# dotclox.net
KiCad netlist of a schematic drawn in EAGLE
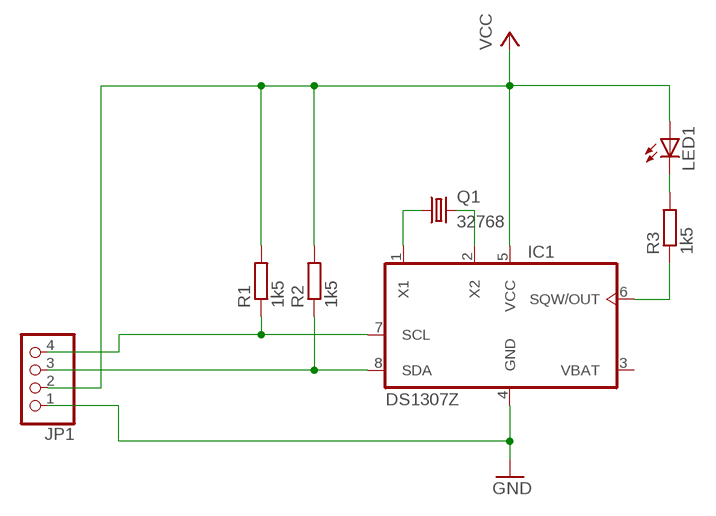
[diagram p0: schematic, sheet 1]

(export (version "E")
  (design (tool "Eeschema 10.0.6"))
  (components
    (comp (ref "IC1")
      (value "DS1307Z")
      (footprint "eagle-import:SO08")
      (libsource (lib "eagle-import") (part "DS1307Z"))
    )
    (comp (ref "JP1")
      (value "PINHD-1X4")
      (footprint "eagle-import:1X04")
      (libsource (lib "eagle-import") (part "PINHD-1X4"))
    )
    (comp (ref "LED1")
      (value "LED3MM")
      (footprint "eagle-import:LED3MM")
      (libsource (lib "eagle-import") (part "LED3MM"))
    )
    (comp (ref "Q1")
      (value "32768")
      (footprint "eagle-import:TC26H")
      (libsource (lib "eagle-import") (part "CRYSTALTC26H"))
    )
    (comp (ref "R1")
      (value "1k5")
      (footprint "eagle-import:R0603")
      (libsource (lib "eagle-import") (part "R-EU_R0603"))
    )
    (comp (ref "R2")
      (value "1k5")
      (footprint "eagle-import:R0603")
      (libsource (lib "eagle-import") (part "R-EU_R0603"))
    )
    (comp (ref "R3")
      (value "1k5")
      (footprint "eagle-import:R0603")
      (libsource (lib "eagle-import") (part "R-EU_R0603"))
    )
  )
  (nets
    (net (code "1") (name "/VBAT") (class "Default")
      (node (ref "IC1") (pin "3") (pinfunction "VBAT_3") (pintype "power_in"))
    )
    (net (code "2") (name "GND") (class "Default")
      (node (ref "IC1") (pin "4") (pinfunction "GND_4") (pintype "power_in"))
      (node (ref "JP1") (pin "1") (pinfunction "1_1") (pintype "passive"))
    )
    (net (code "3") (name "Net-(IC1-SCL)") (class "Default")
      (node (ref "IC1") (pin "7") (pinfunction "SCL_7") (pintype "bidirectional"))
      (node (ref "JP1") (pin "4") (pinfunction "4_4") (pintype "passive"))
      (node (ref "R1") (pin "1") (pinfunction "1_1") (pintype "passive"))
    )
    (net (code "4") (name "Net-(IC1-SDA)") (class "Default")
      (node (ref "IC1") (pin "8") (pinfunction "SDA_8") (pintype "bidirectional"))
      (node (ref "JP1") (pin "3") (pinfunction "3_3") (pintype "passive"))
      (node (ref "R2") (pin "1") (pinfunction "1_1") (pintype "passive"))
    )
    (net (code "5") (name "Net-(IC1-SQW{slash}OUT)") (class "Default")
      (node (ref "IC1") (pin "6") (pinfunction "SQW/OUT_6") (pintype "output"))
      (node (ref "R3") (pin "1") (pinfunction "1_1") (pintype "passive"))
    )
    (net (code "6") (name "Net-(IC1-X1)") (class "Default")
      (node (ref "IC1") (pin "1") (pinfunction "X1_1") (pintype "bidirectional"))
      (node (ref "Q1") (pin "1") (pinfunction "1_1") (pintype "passive"))
    )
    (net (code "7") (name "Net-(IC1-X2)") (class "Default")
      (node (ref "IC1") (pin "2") (pinfunction "X2_2") (pintype "bidirectional"))
      (node (ref "Q1") (pin "2") (pinfunction "2_2") (pintype "passive"))
    )
    (net (code "8") (name "Net-(LED1-C)") (class "Default")
      (node (ref "LED1") (pin "K") (pinfunction "C_K") (pintype "passive"))
      (node (ref "R3") (pin "2") (pinfunction "2_2") (pintype "passive"))
    )
    (net (code "9") (name "VCC") (class "Default")
      (node (ref "IC1") (pin "5") (pinfunction "VCC_5") (pintype "power_in"))
      (node (ref "JP1") (pin "2") (pinfunction "2_2") (pintype "passive"))
      (node (ref "LED1") (pin "A") (pinfunction "A_A") (pintype "passive"))
      (node (ref "R1") (pin "2") (pinfunction "2_2") (pintype "passive"))
      (node (ref "R2") (pin "2") (pinfunction "2_2") (pintype "passive"))
    )
  )
)
